# Temperature_Sensor_Card_Analog.net
KiCad netlist of a schematic drawn in Altium Designer
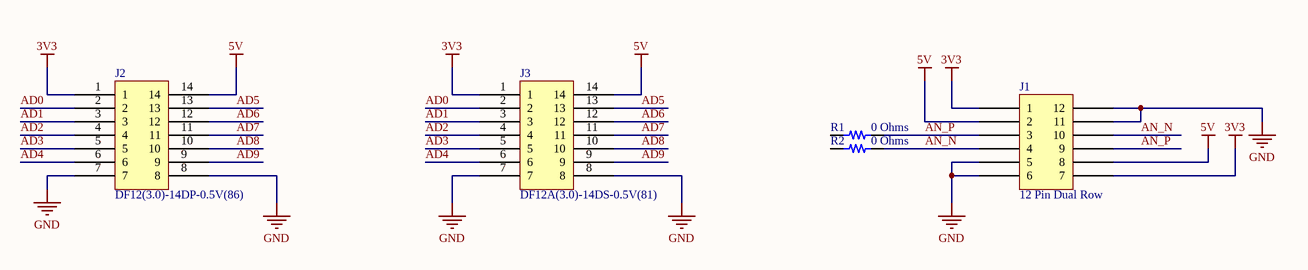
[diagram p0: Temperature Sensor Card Analog.SchDoc]

(export (version "E")
  (design (tool "Eeschema 10.0.6"))
  (components
    (comp (ref "J1")
      (value "12 Pin Dual Row")
      (footprint "TE 5650118-3 Card Edge")
      (libsource (lib "CelestialUseful") (part "12 Pin Dual Row"))
    )
    (comp (ref "J2")
      (value "DF12(3.0)-14DP-0.5V(86)")
      (footprint "HIROSE DF12 3.0-14DP-0.5V 86")
      (description "CONN HDR 14POS SMD GOLD")
      (fields (field (name "MANUFACTURER") "Hirose Electric Co Ltd"))
      (libsource (lib "altiumlibrary.com") (part "14 Pin Dual Row"))
    )
    (comp (ref "J3")
      (value "DF12A(3.0)-14DS-0.5V(81)")
      (footprint "HIROSE DF12A 3.0-14DS-0.5V 81")
      (description "CONN RCPT 14POS SMD GOLD")
      (fields (field (name "MANUFACTURER") "Hirose Electric Co Ltd"))
      (libsource (lib "altiumlibrary.com") (part "14 Pin Dual Row"))
    )
    (comp (ref "R1")
      (value "0 Ohms")
      (footprint "RES 0603_1608")
      (description "RES SMD 0 OHM JUMPER 1/10W 0603")
      (fields
        (field (name "PART NUMBER") "ERJ-3GEY0R00V")
        (field (name "MANUFACTURER") "Panasonic Electronic Components")
      )
      (libsource (lib "altiumlibrary.com") (part "Resistor"))
    )
    (comp (ref "R2")
      (value "0 Ohms")
      (footprint "RES 0603_1608")
      (description "RES SMD 0 OHM JUMPER 1/10W 0603")
      (fields
        (field (name "PART NUMBER") "ERJ-3GEY0R00V")
        (field (name "MANUFACTURER") "Panasonic Electronic Components")
      )
      (libsource (lib "altiumlibrary.com") (part "Resistor"))
    )
  )
  (nets
    (net (code "1") (name "/AD0") (class "Default")
      (node (ref "J2") (pin "2") (pinfunction "2_2") (pintype "passive"))
      (node (ref "J3") (pin "2") (pinfunction "2_2") (pintype "passive"))
    )
    (net (code "2") (name "/AD1") (class "Default")
      (node (ref "J2") (pin "3") (pinfunction "3_3") (pintype "passive"))
      (node (ref "J3") (pin "3") (pinfunction "3_3") (pintype "passive"))
    )
    (net (code "3") (name "/AD2") (class "Default")
      (node (ref "J2") (pin "4") (pinfunction "4_4") (pintype "passive"))
      (node (ref "J3") (pin "4") (pinfunction "4_4") (pintype "passive"))
    )
    (net (code "4") (name "/AD3") (class "Default")
      (node (ref "J2") (pin "5") (pinfunction "5_5") (pintype "passive"))
      (node (ref "J3") (pin "5") (pinfunction "5_5") (pintype "passive"))
    )
    (net (code "5") (name "/AD4") (class "Default")
      (node (ref "J2") (pin "6") (pinfunction "6_6") (pintype "passive"))
      (node (ref "J3") (pin "6") (pinfunction "6_6") (pintype "passive"))
    )
    (net (code "6") (name "/AD5") (class "Default")
      (node (ref "J2") (pin "13") (pinfunction "13_13") (pintype "passive"))
      (node (ref "J3") (pin "13") (pinfunction "13_13") (pintype "passive"))
    )
    (net (code "7") (name "/AD6") (class "Default")
      (node (ref "J2") (pin "12") (pinfunction "12_12") (pintype "passive"))
      (node (ref "J3") (pin "12") (pinfunction "12_12") (pintype "passive"))
    )
    (net (code "8") (name "/AD7") (class "Default")
      (node (ref "J2") (pin "11") (pinfunction "11_11") (pintype "passive"))
      (node (ref "J3") (pin "11") (pinfunction "11_11") (pintype "passive"))
    )
    (net (code "9") (name "/AD8") (class "Default")
      (node (ref "J2") (pin "10") (pinfunction "10_10") (pintype "passive"))
      (node (ref "J3") (pin "10") (pinfunction "10_10") (pintype "passive"))
    )
    (net (code "10") (name "/AD9") (class "Default")
      (node (ref "J2") (pin "9") (pinfunction "9_9") (pintype "passive"))
      (node (ref "J3") (pin "9") (pinfunction "9_9") (pintype "passive"))
    )
    (net (code "11") (name "/AN_N") (class "Default")
      (node (ref "J1") (pin "10") (pinfunction "10_10") (pintype "passive"))
      (node (ref "J1") (pin "4") (pinfunction "4_4") (pintype "passive"))
      (node (ref "R2") (pin "2") (pinfunction "2_2") (pintype "passive"))
    )
    (net (code "12") (name "/AN_P") (class "Default")
      (node (ref "J1") (pin "3") (pinfunction "3_3") (pintype "passive"))
      (node (ref "J1") (pin "9") (pinfunction "9_9") (pintype "passive"))
      (node (ref "R1") (pin "2") (pinfunction "2_2") (pintype "passive"))
    )
    (net (code "13") (name "3V3") (class "Default")
      (node (ref "J1") (pin "1") (pinfunction "1_1") (pintype "passive"))
      (node (ref "J1") (pin "7") (pinfunction "7_7") (pintype "passive"))
      (node (ref "J2") (pin "1") (pinfunction "1_1") (pintype "passive"))
      (node (ref "J3") (pin "1") (pinfunction "1_1") (pintype "passive"))
    )
    (net (code "14") (name "5V") (class "Default")
      (node (ref "J1") (pin "2") (pinfunction "2_2") (pintype "passive"))
      (node (ref "J1") (pin "8") (pinfunction "8_8") (pintype "passive"))
      (node (ref "J2") (pin "14") (pinfunction "14_14") (pintype "passive"))
      (node (ref "J3") (pin "14") (pinfunction "14_14") (pintype "passive"))
    )
    (net (code "15") (name "GND") (class "Default")
      (node (ref "J1") (pin "11") (pinfunction "11_11") (pintype "passive"))
      (node (ref "J1") (pin "12") (pinfunction "12_12") (pintype "passive"))
      (node (ref "J1") (pin "5") (pinfunction "5_5") (pintype "passive"))
      (node (ref "J1") (pin "6") (pinfunction "6_6") (pintype "passive"))
      (node (ref "J2") (pin "7") (pinfunction "7_7") (pintype "passive"))
      (node (ref "J2") (pin "8") (pinfunction "8_8") (pintype "passive"))
      (node (ref "J3") (pin "7") (pinfunction "7_7") (pintype "passive"))
      (node (ref "J3") (pin "8") (pinfunction "8_8") (pintype "passive"))
    )
    (net (code "16") (name "unconnected-(R1-Pad1)") (class "Default")
      (node (ref "R1") (pin "1") (pinfunction "1_1") (pintype "passive"))
    )
    (net (code "17") (name "unconnected-(R2-Pad1)") (class "Default")
      (node (ref "R2") (pin "1") (pinfunction "1_1") (pintype "passive"))
    )
  )
)
